# LDO.net
KiCad netlist of a schematic drawn in Altium Designer
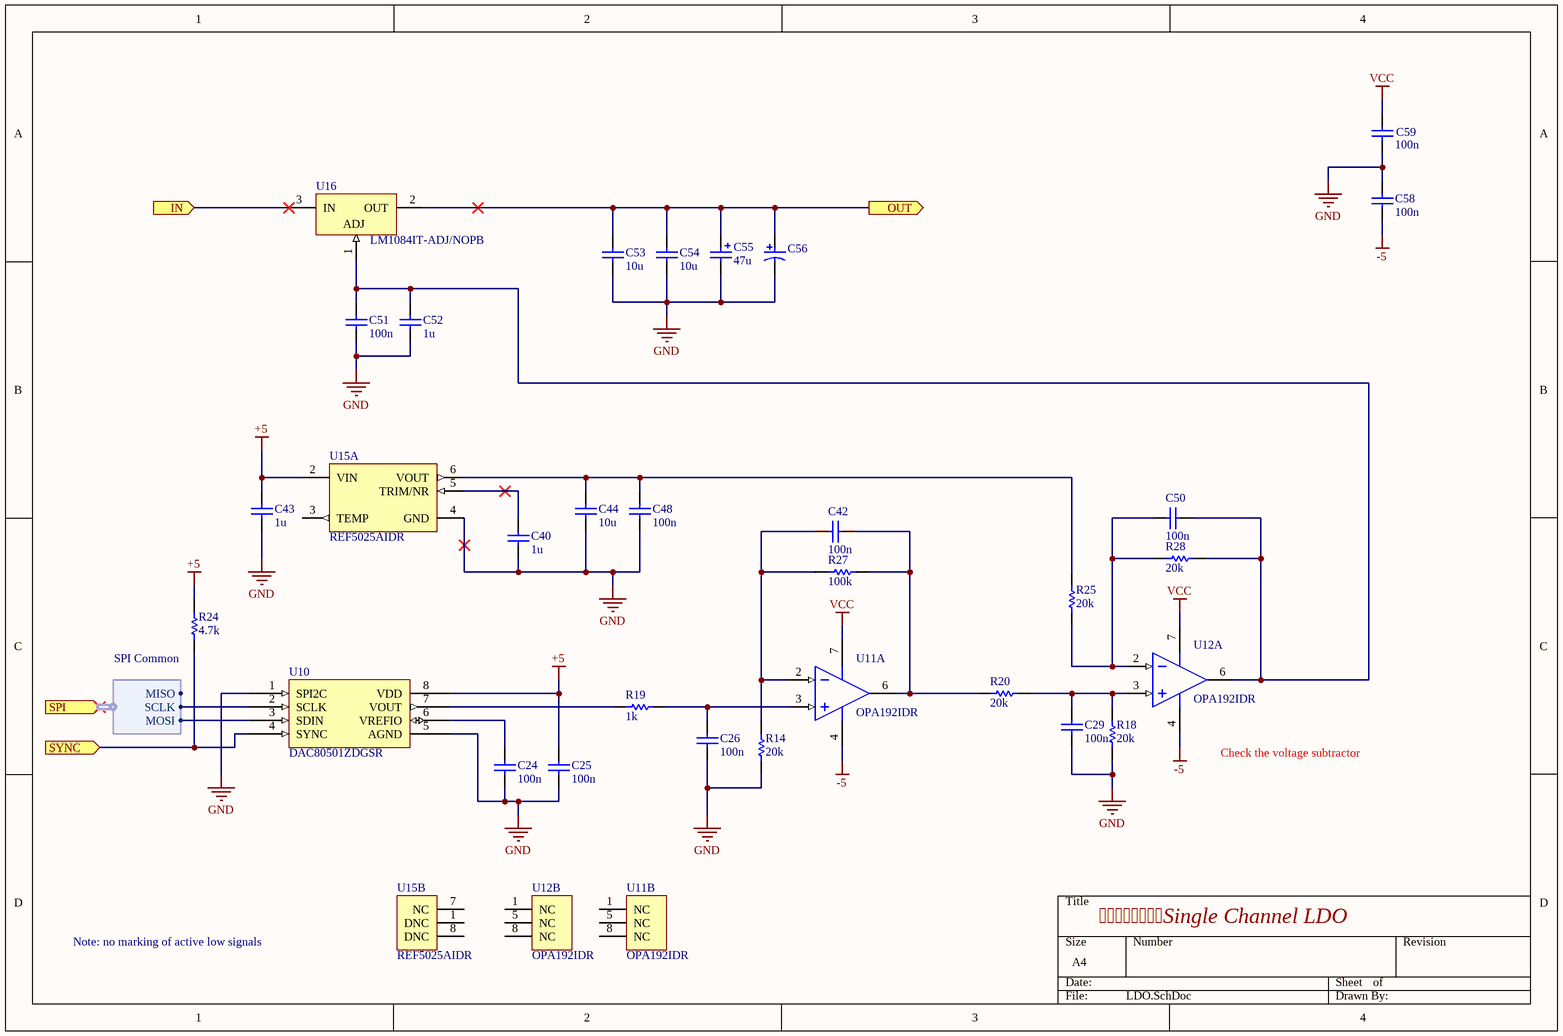
[diagram p0: LDO.SchDoc]

(export (version "E")
  (design (tool "Eeschema 10.0.6"))
  (components
    (comp (ref "C24")
      (value "100n")
      (footprint "CAPC2013X145X50LL20T25")
      (fields (field (name "MANUFACTURER") "Kemet") (field (name "PART NUMBER") "C0805C104K3RALTU"))
      (libsource (lib "Altium Content Vault") (part "CAP"))
    )
    (comp (ref "C25")
      (value "100n")
      (footprint "CAPC2013X145X50LL20T25")
      (fields (field (name "MANUFACTURER") "Kemet") (field (name "PART NUMBER") "C0805C104K3RALTU"))
      (libsource (lib "Altium Content Vault") (part "CAP"))
    )
    (comp (ref "C26")
      (value "100n")
      (footprint "CAPC2013X145X50NL20T25")
      (fields (field (name "MANUFACTURER") "Kemet") (field (name "PART NUMBER") "C0805C104K3RALTU"))
      (libsource (lib "Altium Content Vault") (part "CAP"))
    )
    (comp (ref "C29")
      (value "100n")
      (footprint "CAPC2013X145X50NL20T25")
      (fields (field (name "MANUFACTURER") "Kemet") (field (name "PART NUMBER") "C0805C104K3RALTU"))
      (libsource (lib "Altium Content Vault") (part "CAP"))
    )
    (comp (ref "C40")
      (value "1u")
      (footprint "CAPC2013X140X50LL20T25")
      (fields (field (name "PART NUMBER") "C0805C105K3RACTU") (field (name "MANUFACTURER") "Kemet"))
      (libsource (lib "Altium Content Vault") (part "CAP"))
    )
    (comp (ref "C42")
      (value "100n")
      (footprint "CAPC2013X145X50NL20T25")
      (fields (field (name "MANUFACTURER") "Kemet") (field (name "PART NUMBER") "C0805C104K3RALTU"))
      (libsource (lib "Altium Content Vault") (part "CAP"))
    )
    (comp (ref "C43")
      (value "1u")
      (footprint "CAPC2013X140X50LL20T25")
      (fields (field (name "PART NUMBER") "C0805C105K3RACTU") (field (name "MANUFACTURER") "Kemet"))
      (libsource (lib "Altium Content Vault") (part "CAP"))
    )
    (comp (ref "C44")
      (value "10u")
      (footprint "CAPC3216X180X55LL20T30")
      (fields (field (name "MANUFACTURER") "Taiyo Yuden") (field (name "TOLERANCE") "±10%"))
      (libsource (lib "Altium Content Vault") (part "CAP-NP-2"))
    )
    (comp (ref "C48")
      (value "100n")
      (footprint "CAPC2013X145X50LL20T25")
      (fields (field (name "MANUFACTURER") "Kemet") (field (name "PART NUMBER") "C0805C104K3RALTU"))
      (libsource (lib "Altium Content Vault") (part "CAP"))
    )
    (comp (ref "C50")
      (value "100n")
      (footprint "CAPC2013X145X50NL20T25")
      (fields (field (name "MANUFACTURER") "Kemet") (field (name "PART NUMBER") "C0805C104K3RALTU"))
      (libsource (lib "Altium Content Vault") (part "CAP"))
    )
    (comp (ref "C51")
      (value "100n")
      (footprint "CAPC2013X145X50LL20T25")
      (fields (field (name "MANUFACTURER") "Kemet") (field (name "PART NUMBER") "C0805C104K3RALTU"))
      (libsource (lib "Altium Content Vault") (part "CAP"))
    )
    (comp (ref "C52")
      (value "1u")
      (footprint "CAPC2013X140X50LL20T25")
      (fields (field (name "PART NUMBER") "C0805C105K3RACTU") (field (name "MANUFACTURER") "Kemet"))
      (libsource (lib "Altium Content Vault") (part "CAP"))
    )
    (comp (ref "C53")
      (value "10u")
      (footprint "CAPC3216X180X55LL20T30")
      (fields (field (name "MANUFACTURER") "Taiyo Yuden") (field (name "TOLERANCE") "±10%"))
      (libsource (lib "Altium Content Vault") (part "CAP-NP-2"))
    )
    (comp (ref "C54")
      (value "10u")
      (footprint "CAPC3216X180X55LL20T30")
      (fields (field (name "MANUFACTURER") "Taiyo Yuden") (field (name "TOLERANCE") "±10%"))
      (libsource (lib "Altium Content Vault") (part "CAP-NP-2"))
    )
    (comp (ref "C55")
      (value "47u")
      (footprint "7343")
      (description "KEMET - T521X476M035ATE030 - CAP, TANT, POLYMER, 47UF, 35V, CASE X")
      (fields
        (field (name "MANUFACTURER") "KEMET")
        (field (name "MANUFACTURER PART NUMBER") "T521X476M035ATE030")
      )
      (libsource (lib "PPS Lib") (part "T521X476M035ATE030"))
    )
    (comp (ref "C56")
      (value "ECA-1JHG471")
      (footprint "CAPPR65-500-2000X1250X2200")
      (fields (field (name "MANUFACTURER") "Panasonic"))
      (libsource (lib "Altium Content Vault") (part "CAP-P-2"))
    )
    (comp (ref "C58")
      (value "100n")
      (footprint "CAPC2013X145X50LL20T25")
      (fields (field (name "MANUFACTURER") "Kemet") (field (name "PART NUMBER") "C0805C104K3RALTU"))
      (libsource (lib "Altium Content Vault") (part "CAP"))
    )
    (comp (ref "C59")
      (value "100n")
      (footprint "CAPC2013X145X50LL20T25")
      (fields (field (name "MANUFACTURER") "Kemet") (field (name "PART NUMBER") "C0805C104K3RALTU"))
      (libsource (lib "Altium Content Vault") (part "CAP"))
    )
    (comp (ref "R14")
      (value "20k")
      (footprint "RESC2013X70X40NL20T20")
      (fields (field (name "MANUFACTURER") "Panasonic") (field (name "PART NUMBER") "ERJ-6GEYJ203V"))
      (libsource (lib "Altium Content Vault") (part "RES"))
    )
    (comp (ref "R18")
      (value "20k")
      (footprint "RESC2013X70X40NL20T20")
      (fields (field (name "MANUFACTURER") "Panasonic") (field (name "PART NUMBER") "ERJ-6GEYJ203V"))
      (libsource (lib "Altium Content Vault") (part "RES"))
    )
    (comp (ref "R19")
      (value "1k")
      (footprint "RESC2013X50X30NL20T20")
      (fields (field (name "PART NUMBER") "CRCW08051K00FKEA") (field (name "MANUFACTURER") "Vishay Dale"))
      (libsource (lib "Altium Content Vault") (part "RES"))
    )
    (comp (ref "R20")
      (value "20k")
      (footprint "RESC2013X70X40NL20T20")
      (fields (field (name "MANUFACTURER") "Panasonic") (field (name "PART NUMBER") "ERJ-6GEYJ203V"))
      (libsource (lib "Altium Content Vault") (part "RES"))
    )
    (comp (ref "R24")
      (value "4.7k")
      (footprint "RESC2013X70X40NL20T20")
      (fields (field (name "MANUFACTURER") "Panasonic") (field (name "PART NUMBER") "ERJ-6GEYJ472V"))
      (libsource (lib "Altium Content Vault") (part "RES"))
    )
    (comp (ref "R25")
      (value "20k")
      (footprint "RESC2013X70X40NL20T20")
      (fields (field (name "MANUFACTURER") "Panasonic") (field (name "PART NUMBER") "ERJ-6GEYJ203V"))
      (libsource (lib "Altium Content Vault") (part "RES"))
    )
    (comp (ref "R27")
      (value "100k")
      (footprint "RESC2013X70X40NL20T20")
      (fields (field (name "PART NUMBER") "ERJ-6GEYJ104V") (field (name "MANUFACTURER") "Panasonic"))
      (libsource (lib "Altium Content Vault") (part "RES"))
    )
    (comp (ref "R28")
      (value "20k")
      (footprint "RESC2013X70X40NL20T20")
      (fields (field (name "MANUFACTURER") "Panasonic") (field (name "PART NUMBER") "ERJ-6GEYJ203V"))
      (libsource (lib "Altium Content Vault") (part "RES"))
    )
    (comp (ref "U10")
      (value "DAC80501ZDGSR")
      (footprint "MSOP10")
      (fields
        (field (name "MANUFACTURER") "Texas Instruments")
        (field (name "MANUFACTURER PART NUMBER") "DAC80501ZDGSR")
      )
      (libsource (lib "PPS Lib") (part "DAC80501ZDGSR"))
    )
    (comp (ref "U11")
      (value "OPA192IDR")
      (footprint "D0008A_M")
      (libsource (lib "Altium Content Vault") (part "TI-OPA192-8"))
    )
    (comp (ref "U12")
      (value "OPA192IDR")
      (footprint "D0008A_M")
      (libsource (lib "Altium Content Vault") (part "TI-OPA192-8"))
    )
    (comp (ref "U15")
      (value "REF5025AIDR")
      (footprint "D0008A_L")
      (fields (field (name "MANUFACTURER") "Texas Instruments"))
      (libsource (lib "Altium Content Vault") (part "TI-REF5025D8"))
    )
    (comp (ref "U16")
      (value "LM1084IT-ADJ/NOPB")
      (footprint "NDE0003A")
      (description "5A Low Dropout Positive Regulators, 3-pin TO-220, Pb-Free")
      (fields (field (name "MANUFACTURER") "Texas Instruments"))
      (libsource (lib "Altium Content Vault") (part "PM-REG-LM1086ADJ-SIL3"))
    )
  )
  (nets
    (net (code "3") (name "+5") (class "Default")
      (node (ref "C25") (pin "1") (pinfunction "1_1") (pintype "passive"))
      (node (ref "C43") (pin "2") (pinfunction "2_2") (pintype "passive"))
      (node (ref "R24") (pin "2") (pinfunction "2_2") (pintype "passive"))
      (node (ref "U10") (pin "8") (pinfunction "VDD_8") (pintype "power_in"))
      (node (ref "U15") (pin "2") (pinfunction "VIN_2") (pintype "power_in"))
    )
    (net (code "4") (name "-5") (class "Default")
      (node (ref "C58") (pin "2") (pinfunction "2_2") (pintype "passive"))
      (node (ref "U11") (pin "4") (pinfunction "V-_4") (pintype "power_in"))
      (node (ref "U12") (pin "4") (pinfunction "V-_4") (pintype "power_in"))
    )
    (net (code "5") (name "/IN") (class "Default")
      (node (ref "U16") (pin "3") (pinfunction "IN_3") (pintype "power_in+no_connect"))
    )
    (net (code "6") (name "/MOSI") (class "Default")
      (node (ref "U10") (pin "3") (pinfunction "SDIN_3") (pintype "input"))
    )
    (net (code "7") (name "/OUT") (class "Default")
      (node (ref "C53") (pin "2") (pinfunction "2_2") (pintype "passive"))
      (node (ref "C54") (pin "2") (pinfunction "2_2") (pintype "passive"))
      (node (ref "C55") (pin "1") (pinfunction "1_1") (pintype "passive"))
      (node (ref "C56") (pin "1") (pinfunction "1_1") (pintype "passive"))
      (node (ref "U16") (pin "2") (pinfunction "OUT_2") (pintype "power_in"))
    )
    (net (code "8") (name "/SCLK") (class "Default")
      (node (ref "U10") (pin "2") (pinfunction "SCLK_2") (pintype "input"))
    )
    (net (code "9") (name "/SYNC") (class "Default")
      (node (ref "R24") (pin "1") (pinfunction "1_1") (pintype "passive"))
      (node (ref "U10") (pin "4") (pinfunction "SYNC_4") (pintype "input"))
    )
    (net (code "11") (name "GND") (class "Default")
      (node (ref "C24") (pin "2") (pinfunction "2_2") (pintype "passive"))
      (node (ref "C25") (pin "2") (pinfunction "2_2") (pintype "passive"))
      (node (ref "C26") (pin "2") (pinfunction "2_2") (pintype "passive"))
      (node (ref "C29") (pin "2") (pinfunction "2_2") (pintype "passive"))
      (node (ref "C40") (pin "1") (pinfunction "1_1") (pintype "passive"))
      (node (ref "C43") (pin "1") (pinfunction "1_1") (pintype "passive"))
      (node (ref "C44") (pin "1") (pinfunction "1_1") (pintype "passive"))
      (node (ref "C48") (pin "2") (pinfunction "2_2") (pintype "passive"))
      (node (ref "C51") (pin "2") (pinfunction "2_2") (pintype "passive"))
      (node (ref "C52") (pin "1") (pinfunction "1_1") (pintype "passive"))
      (node (ref "C53") (pin "1") (pinfunction "1_1") (pintype "passive"))
      (node (ref "C54") (pin "1") (pinfunction "1_1") (pintype "passive"))
      (node (ref "C55") (pin "2") (pinfunction "2_2") (pintype "passive"))
      (node (ref "C56") (pin "2") (pinfunction "2_2") (pintype "passive"))
      (node (ref "C58") (pin "1") (pinfunction "1_1") (pintype "passive"))
      (node (ref "C59") (pin "2") (pinfunction "2_2") (pintype "passive"))
      (node (ref "R14") (pin "1") (pinfunction "1_1") (pintype "passive"))
      (node (ref "R18") (pin "1") (pinfunction "1_1") (pintype "passive"))
      (node (ref "U10") (pin "1") (pinfunction "SPI2C_1") (pintype "input"))
      (node (ref "U10") (pin "5") (pinfunction "AGND_5") (pintype "passive"))
      (node (ref "U15") (pin "4") (pinfunction "GND_4") (pintype "power_in"))
    )
    (net (code "12") (name "Net-(U10-VOUT)") (class "Default")
      (node (ref "R19") (pin "2") (pinfunction "2_2") (pintype "passive"))
      (node (ref "U10") (pin "7") (pinfunction "VOUT_7") (pintype "output"))
    )
    (net (code "13") (name "Net-(U10-VREFIO)") (class "Default")
      (node (ref "C24") (pin "1") (pinfunction "1_1") (pintype "passive"))
      (node (ref "U10") (pin "6") (pinfunction "VREFIO_6") (pintype "bidirectional"))
    )
    (net (code "14") (name "Net-(U11A-IN+)") (class "Default")
      (node (ref "C26") (pin "1") (pinfunction "1_1") (pintype "passive"))
      (node (ref "R19") (pin "1") (pinfunction "1_1") (pintype "passive"))
      (node (ref "U11") (pin "3") (pinfunction "IN+_3") (pintype "input"))
    )
    (net (code "15") (name "Net-(U11A-IN-)") (class "Default")
      (node (ref "C42") (pin "2") (pinfunction "2_2") (pintype "passive"))
      (node (ref "R14") (pin "2") (pinfunction "2_2") (pintype "passive"))
      (node (ref "R27") (pin "1") (pinfunction "1_1") (pintype "passive"))
      (node (ref "U11") (pin "2") (pinfunction "IN-_2") (pintype "input"))
    )
    (net (code "16") (name "Net-(U11A-OUT)") (class "Default")
      (node (ref "C42") (pin "1") (pinfunction "1_1") (pintype "passive"))
      (node (ref "R20") (pin "1") (pinfunction "1_1") (pintype "passive"))
      (node (ref "R27") (pin "2") (pinfunction "2_2") (pintype "passive"))
      (node (ref "U11") (pin "6") (pinfunction "OUT_6") (pintype "tri_state"))
    )
    (net (code "17") (name "Net-(U12A-IN+)") (class "Default")
      (node (ref "C29") (pin "1") (pinfunction "1_1") (pintype "passive"))
      (node (ref "R18") (pin "2") (pinfunction "2_2") (pintype "passive"))
      (node (ref "R20") (pin "2") (pinfunction "2_2") (pintype "passive"))
      (node (ref "U12") (pin "3") (pinfunction "IN+_3") (pintype "input"))
    )
    (net (code "18") (name "Net-(U12A-IN-)") (class "Default")
      (node (ref "C50") (pin "2") (pinfunction "2_2") (pintype "passive"))
      (node (ref "R25") (pin "1") (pinfunction "1_1") (pintype "passive"))
      (node (ref "R28") (pin "2") (pinfunction "2_2") (pintype "passive"))
      (node (ref "U12") (pin "2") (pinfunction "IN-_2") (pintype "input"))
    )
    (net (code "19") (name "Net-(U12A-OUT)") (class "Default")
      (node (ref "C50") (pin "1") (pinfunction "1_1") (pintype "passive"))
      (node (ref "C51") (pin "1") (pinfunction "1_1") (pintype "passive"))
      (node (ref "C52") (pin "2") (pinfunction "2_2") (pintype "passive"))
      (node (ref "R28") (pin "1") (pinfunction "1_1") (pintype "passive"))
      (node (ref "U12") (pin "6") (pinfunction "OUT_6") (pintype "tri_state"))
      (node (ref "U16") (pin "1") (pinfunction "ADJ_1") (pintype "input"))
    )
    (net (code "20") (name "Net-(U15A-TRIM{slash}NR)") (class "Default")
      (node (ref "C40") (pin "2") (pinfunction "2_2") (pintype "passive"))
      (node (ref "U15") (pin "5") (pinfunction "TRIM/NR_5") (pintype "input"))
    )
    (net (code "21") (name "Net-(U15A-VOUT)") (class "Default")
      (node (ref "C44") (pin "2") (pinfunction "2_2") (pintype "passive"))
      (node (ref "C48") (pin "1") (pinfunction "1_1") (pintype "passive"))
      (node (ref "R25") (pin "2") (pinfunction "2_2") (pintype "passive"))
      (node (ref "U15") (pin "6") (pinfunction "VOUT_6") (pintype "output"))
    )
    (net (code "22") (name "VCC") (class "Default")
      (node (ref "C59") (pin "1") (pinfunction "1_1") (pintype "passive"))
      (node (ref "U11") (pin "7") (pinfunction "V+_7") (pintype "power_in"))
      (node (ref "U12") (pin "7") (pinfunction "V+_7") (pintype "power_in"))
    )
    (net (code "23") (name "unconnected-(U11B-NC-Pad1)") (class "Default")
      (node (ref "U11") (pin "1") (pinfunction "NC_1") (pintype "passive"))
    )
    (net (code "24") (name "unconnected-(U11B-NC-Pad5)") (class "Default")
      (node (ref "U11") (pin "5") (pinfunction "NC_5") (pintype "passive"))
    )
    (net (code "25") (name "unconnected-(U11B-NC-Pad8)") (class "Default")
      (node (ref "U11") (pin "8") (pinfunction "NC_8") (pintype "passive"))
    )
    (net (code "26") (name "unconnected-(U12B-NC-Pad1)") (class "Default")
      (node (ref "U12") (pin "1") (pinfunction "NC_1") (pintype "passive"))
    )
    (net (code "27") (name "unconnected-(U12B-NC-Pad5)") (class "Default")
      (node (ref "U12") (pin "5") (pinfunction "NC_5") (pintype "passive"))
    )
    (net (code "28") (name "unconnected-(U12B-NC-Pad8)") (class "Default")
      (node (ref "U12") (pin "8") (pinfunction "NC_8") (pintype "passive"))
    )
    (net (code "29") (name "unconnected-(U15A-TEMP-Pad3)") (class "Default")
      (node (ref "U15") (pin "3") (pinfunction "TEMP_3") (pintype "output"))
    )
    (net (code "30") (name "unconnected-(U15B-DNC-Pad1)") (class "Default")
      (node (ref "U15") (pin "1") (pinfunction "DNC_1") (pintype "passive"))
    )
    (net (code "31") (name "unconnected-(U15B-DNC-Pad8)") (class "Default")
      (node (ref "U15") (pin "8") (pinfunction "DNC_8") (pintype "passive"))
    )
    (net (code "32") (name "unconnected-(U15B-NC-Pad7)") (class "Default")
      (node (ref "U15") (pin "7") (pinfunction "NC_7") (pintype "passive"))
    )
  )
)
